# SparkFun_ProtoShield_Kit.net
KiCad netlist of a schematic drawn in EAGLE
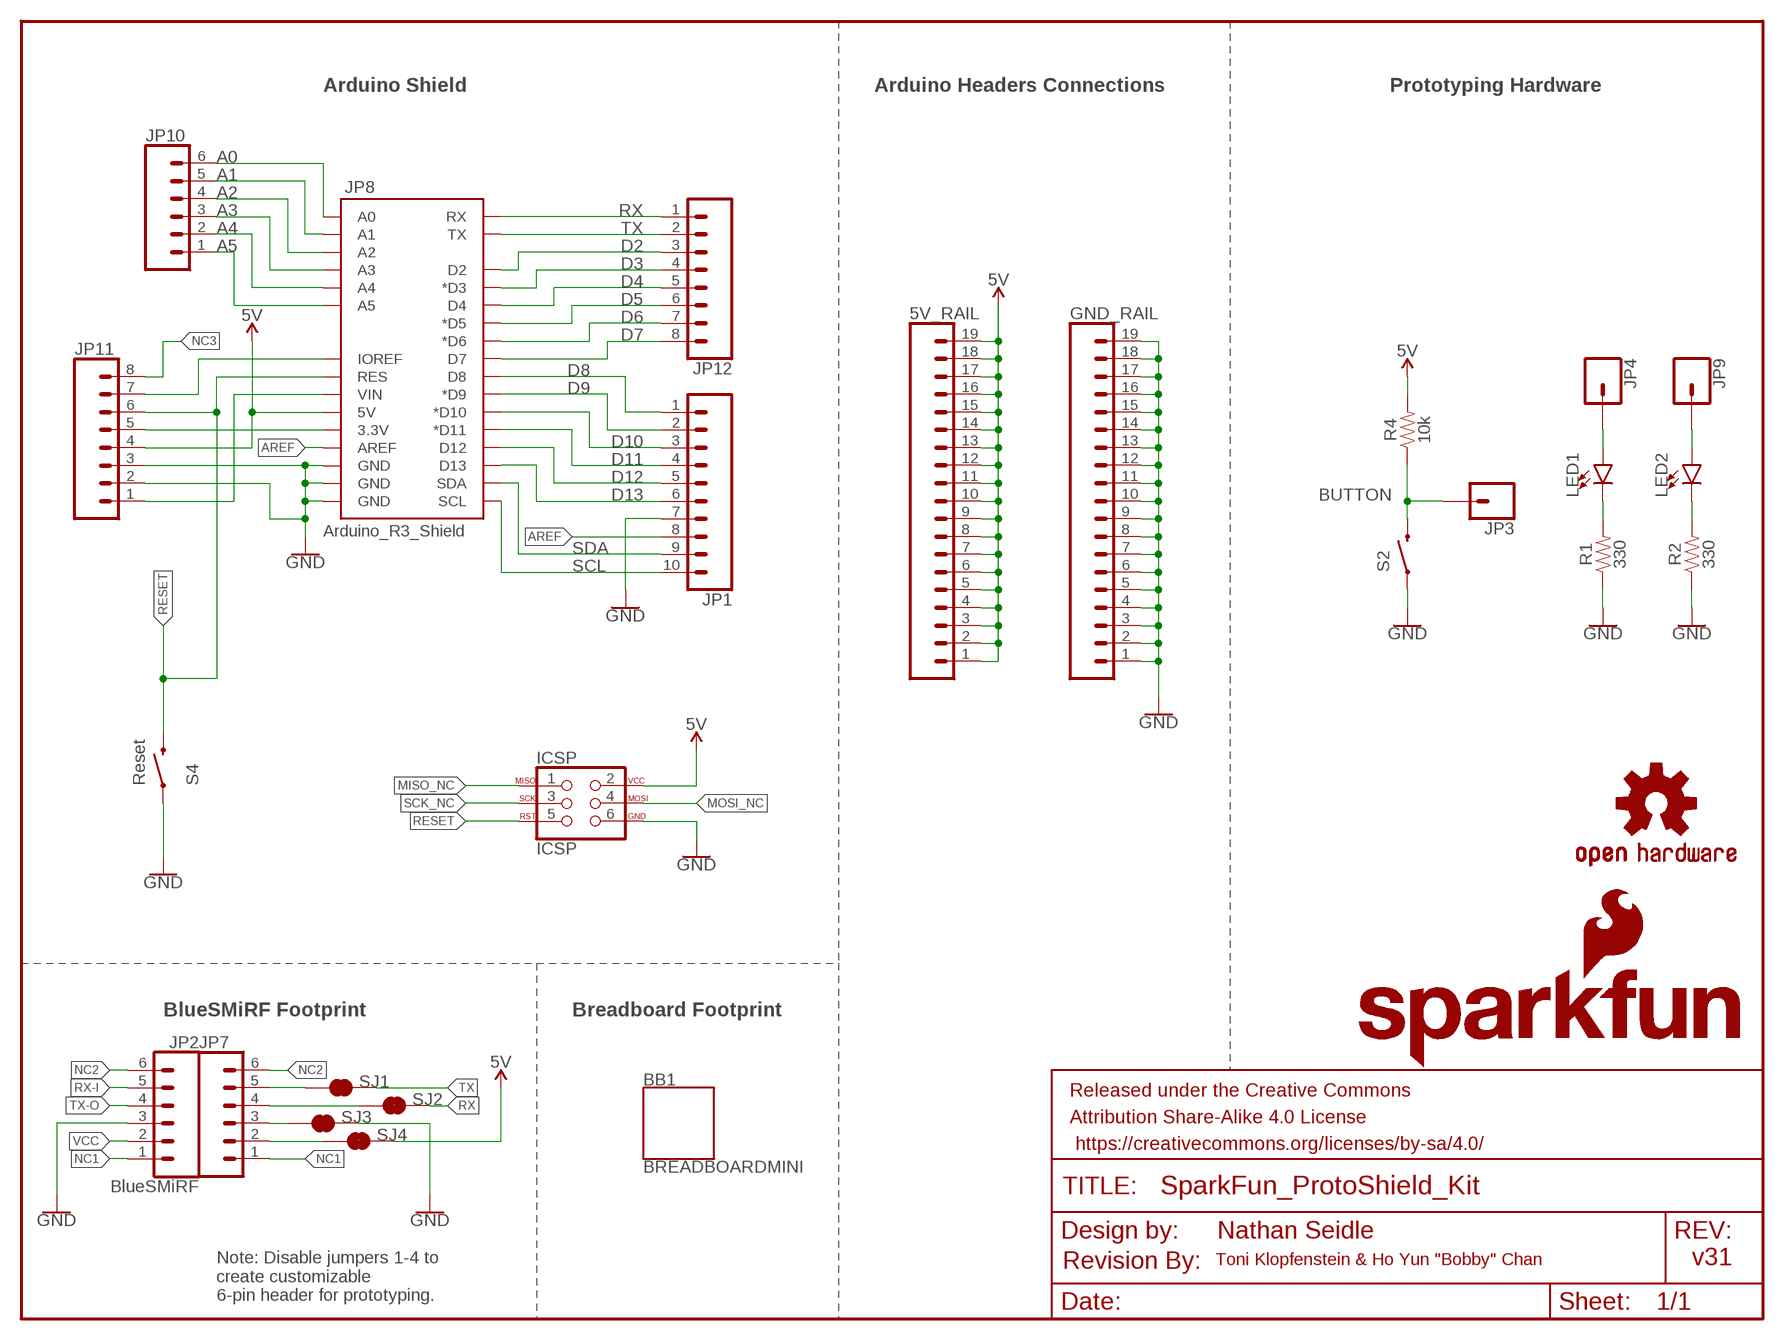
[diagram p0: schematic, sheet 1]

(export (version "E")
  (design (tool "Eeschema 10.0.6"))
  (components
    (comp (ref "5V_RAIL")
      (value "CONN_19")
      (footprint "eagle-import:1X19")
      (libsource (lib "eagle-import") (part "CONN_19"))
    )
    (comp (ref "BB1")
      (value "BREADBOARDMINI")
      (footprint "eagle-import:BREADBOARD-MINI")
      (libsource (lib "eagle-import") (part "BREADBOARDMINI"))
    )
    (comp (ref "FRAME1")
      (value "FRAME-LETTER")
      (footprint "eagle-import:CREATIVE_COMMONS")
      (libsource (lib "eagle-import") (part "FRAME-LETTER"))
    )
    (comp (ref "GND_RAIL")
      (value "CONN_19")
      (footprint "eagle-import:1X19")
      (libsource (lib "eagle-import") (part "CONN_19"))
    )
    (comp (ref "ICSP")
      (value "ICSP")
      (footprint "eagle-import:2X3")
      (libsource (lib "eagle-import") (part "AVR_SPI_PROG_3X2PTH"))
    )
    (comp (ref "JP1")
      (value "CONN_10\"")
      (footprint "eagle-import:1X10")
      (libsource (lib "eagle-import") (part "CONN_10{dblquote}"))
    )
    (comp (ref "JP2")
      (value "BlueSMiRF")
      (footprint "eagle-import:1X06")
      (libsource (lib "eagle-import") (part "CONN_06SILK_FEMALE_PTH"))
    )
    (comp (ref "JP3")
      (value "CONN_01")
      (footprint "eagle-import:1X01")
      (libsource (lib "eagle-import") (part "CONN_01"))
    )
    (comp (ref "JP4")
      (value "CONN_01")
      (footprint "eagle-import:1X01")
      (libsource (lib "eagle-import") (part "CONN_01"))
    )
    (comp (ref "JP7")
      (value "CONN_06SILK_FEMALE_PTH")
      (footprint "eagle-import:1X06")
      (libsource (lib "eagle-import") (part "CONN_06SILK_FEMALE_PTH"))
    )
    (comp (ref "JP8")
      (value "ARDUINO_R3_SHIELDR3_PROTO_SHIELD")
      (footprint "eagle-import:UNO_R3_PROTO_SHIELD")
      (libsource (lib "eagle-import") (part "ARDUINO_R3_SHIELDR3_PROTO_SHIELD"))
    )
    (comp (ref "JP9")
      (value "CONN_01")
      (footprint "eagle-import:1X01")
      (libsource (lib "eagle-import") (part "CONN_01"))
    )
    (comp (ref "JP10")
      (value "CONN_06SILK_FEMALE_PTH")
      (footprint "eagle-import:1X06")
      (libsource (lib "eagle-import") (part "CONN_06SILK_FEMALE_PTH"))
    )
    (comp (ref "JP11")
      (value "CONN_08\"")
      (footprint "eagle-import:1X08")
      (libsource (lib "eagle-import") (part "CONN_08{dblquote}"))
    )
    (comp (ref "JP12")
      (value "CONN_08\"")
      (footprint "eagle-import:1X08")
      (libsource (lib "eagle-import") (part "CONN_08{dblquote}"))
    )
    (comp (ref "LED1")
      (value "LED3MM")
      (footprint "eagle-import:LED_3MM")
      (libsource (lib "eagle-import") (part "LED3MM"))
    )
    (comp (ref "LED2")
      (value "LED3MM")
      (footprint "eagle-import:LED_3MM")
      (libsource (lib "eagle-import") (part "LED3MM"))
    )
    (comp (ref "LOGO1")
      (value "OSHW-LOGOS")
      (footprint "eagle-import:OSHW-LOGO-S")
      (libsource (lib "eagle-import") (part "OSHW-LOGOS"))
    )
    (comp (ref "R1")
      (value "330")
      (footprint "eagle-import:AXIAL-0.3")
      (libsource (lib "eagle-import") (part "330OHM-HORIZ-1/10W-5%"))
    )
    (comp (ref "R2")
      (value "330")
      (footprint "eagle-import:AXIAL-0.3")
      (libsource (lib "eagle-import") (part "330OHM-HORIZ-1/10W-5%"))
    )
    (comp (ref "R4")
      (value "10k")
      (footprint "eagle-import:AXIAL-0.3")
      (libsource (lib "eagle-import") (part "10KOHM-HORIZ-1/4W-5%"))
    )
    (comp (ref "S2")
      (value "MOMENTARY-SWITCH-SPST-PTH-6.0MM-KIT")
      (footprint "eagle-import:TACTILE_SWITCH_PTH_6.0MM_KIT")
      (libsource (lib "eagle-import") (part "MOMENTARY-SWITCH-SPST-PTH-6.0MM-KIT"))
    )
    (comp (ref "S4")
      (value "MOMENTARY-SWITCH-SPST-PTH-6.0MM-KIT")
      (footprint "eagle-import:TACTILE_SWITCH_PTH_6.0MM_KIT")
      (libsource (lib "eagle-import") (part "MOMENTARY-SWITCH-SPST-PTH-6.0MM-KIT"))
    )
    (comp (ref "SJ1")
      (value "JUMPER-SMT_2_NC_TRACE_SILK")
      (footprint "eagle-import:SMT-JUMPER_2_NC_TRACE_SILK")
      (libsource (lib "eagle-import") (part "JUMPER-SMT_2_NC_TRACE_SILK"))
    )
    (comp (ref "SJ2")
      (value "JUMPER-SMT_2_NC_TRACE_SILK")
      (footprint "eagle-import:SMT-JUMPER_2_NC_TRACE_SILK")
      (libsource (lib "eagle-import") (part "JUMPER-SMT_2_NC_TRACE_SILK"))
    )
    (comp (ref "SJ3")
      (value "JUMPER-SMT_2_NC_TRACE_SILK")
      (footprint "eagle-import:SMT-JUMPER_2_NC_TRACE_SILK")
      (libsource (lib "eagle-import") (part "JUMPER-SMT_2_NC_TRACE_SILK"))
    )
    (comp (ref "SJ4")
      (value "JUMPER-SMT_2_NC_TRACE_SILK")
      (footprint "eagle-import:SMT-JUMPER_2_NC_TRACE_SILK")
      (libsource (lib "eagle-import") (part "JUMPER-SMT_2_NC_TRACE_SILK"))
    )
    (comp (ref "U$1")
      (value "SFE_LOGO_NAME_FLAME.1_INCH")
      (footprint "eagle-import:SFE_LOGO_NAME_FLAME_.1")
      (libsource (lib "eagle-import") (part "SFE_LOGO_NAME_FLAME.1_INCH"))
    )
    (comp (ref "U$2")
      (value "REVISION")
      (footprint "eagle-import:REVISION")
      (libsource (lib "eagle-import") (part "REVISION"))
    )
  )
  (nets
    (net (code "1") (name "/BUTTON") (class "Default")
      (node (ref "JP3") (pin "1") (pinfunction "1_1") (pintype "passive"))
      (node (ref "R4") (pin "P$1") (pinfunction "1_P$1") (pintype "passive"))
      (node (ref "S2") (pin "3") (pinfunction "2_3") (pintype "passive"))
    )
    (net (code "2") (name "/D2") (class "Default")
      (node (ref "JP12") (pin "3") (pinfunction "3_3") (pintype "passive"))
      (node (ref "JP8") (pin "D2") (pinfunction "D2_D2") (pintype "bidirectional"))
    )
    (net (code "3") (name "/D3") (class "Default")
      (node (ref "JP12") (pin "4") (pinfunction "4_4") (pintype "passive"))
      (node (ref "JP8") (pin "D3") (pinfunction "*D3_D3") (pintype "bidirectional"))
    )
    (net (code "4") (name "/D4") (class "Default")
      (node (ref "JP12") (pin "5") (pinfunction "5_5") (pintype "passive"))
      (node (ref "JP8") (pin "D4") (pinfunction "D4_D4") (pintype "bidirectional"))
    )
    (net (code "5") (name "/D5") (class "Default")
      (node (ref "JP12") (pin "6") (pinfunction "6_6") (pintype "passive"))
      (node (ref "JP8") (pin "D5") (pinfunction "*D5_D5") (pintype "bidirectional"))
    )
    (net (code "6") (name "/D6") (class "Default")
      (node (ref "JP12") (pin "7") (pinfunction "7_7") (pintype "passive"))
      (node (ref "JP8") (pin "D6") (pinfunction "*D6_D6") (pintype "bidirectional"))
    )
    (net (code "7") (name "/D7") (class "Default")
      (node (ref "JP12") (pin "8") (pinfunction "8_8") (pintype "passive"))
      (node (ref "JP8") (pin "D7") (pinfunction "D7_D7") (pintype "bidirectional"))
    )
    (net (code "8") (name "/D8") (class "Default")
      (node (ref "JP1") (pin "1") (pinfunction "1_1") (pintype "passive"))
      (node (ref "JP8") (pin "D8") (pinfunction "D8_D8") (pintype "bidirectional"))
    )
    (net (code "9") (name "/D9") (class "Default")
      (node (ref "JP1") (pin "2") (pinfunction "2_2") (pintype "passive"))
      (node (ref "JP8") (pin "D9") (pinfunction "*D9_D9") (pintype "bidirectional"))
    )
    (net (code "10") (name "/D10") (class "Default")
      (node (ref "JP1") (pin "3") (pinfunction "3_3") (pintype "passive"))
      (node (ref "JP8") (pin "D10") (pinfunction "*D10_D10") (pintype "bidirectional"))
    )
    (net (code "11") (name "/D11") (class "Default")
      (node (ref "JP1") (pin "4") (pinfunction "4_4") (pintype "passive"))
      (node (ref "JP8") (pin "D11") (pinfunction "*D11_D11") (pintype "bidirectional"))
    )
    (net (code "12") (name "/D12") (class "Default")
      (node (ref "JP1") (pin "5") (pinfunction "5_5") (pintype "passive"))
      (node (ref "JP8") (pin "D12") (pinfunction "D12_D12") (pintype "bidirectional"))
    )
    (net (code "13") (name "/D13") (class "Default")
      (node (ref "JP1") (pin "6") (pinfunction "6_6") (pintype "passive"))
      (node (ref "JP8") (pin "D13") (pinfunction "D13_D13") (pintype "bidirectional"))
    )
    (net (code "14") (name "/SCL") (class "Default")
      (node (ref "JP1") (pin "10") (pinfunction "10_10") (pintype "passive"))
      (node (ref "JP8") (pin "SCL") (pinfunction "SCL_SCL") (pintype "bidirectional"))
    )
    (net (code "15") (name "/SDA") (class "Default")
      (node (ref "JP1") (pin "9") (pinfunction "9_9") (pintype "passive"))
      (node (ref "JP8") (pin "SDA") (pinfunction "SDA_SDA") (pintype "bidirectional"))
    )
    (net (code "16") (name "5V") (class "Default")
      (node (ref "5V_RAIL") (pin "1") (pinfunction "1_1") (pintype "passive"))
      (node (ref "5V_RAIL") (pin "10") (pinfunction "10_10") (pintype "passive"))
      (node (ref "5V_RAIL") (pin "11") (pinfunction "11_11") (pintype "passive"))
      (node (ref "5V_RAIL") (pin "12") (pinfunction "12_12") (pintype "passive"))
      (node (ref "5V_RAIL") (pin "13") (pinfunction "13_13") (pintype "passive"))
      (node (ref "5V_RAIL") (pin "14") (pinfunction "14_14") (pintype "passive"))
      (node (ref "5V_RAIL") (pin "15") (pinfunction "15_15") (pintype "passive"))
      (node (ref "5V_RAIL") (pin "16") (pinfunction "16_16") (pintype "passive"))
      (node (ref "5V_RAIL") (pin "17") (pinfunction "17_17") (pintype "passive"))
      (node (ref "5V_RAIL") (pin "18") (pinfunction "18_18") (pintype "passive"))
      (node (ref "5V_RAIL") (pin "19") (pinfunction "19_19") (pintype "passive"))
      (node (ref "5V_RAIL") (pin "2") (pinfunction "2_2") (pintype "passive"))
      (node (ref "5V_RAIL") (pin "3") (pinfunction "3_3") (pintype "passive"))
      (node (ref "5V_RAIL") (pin "4") (pinfunction "4_4") (pintype "passive"))
      (node (ref "5V_RAIL") (pin "5") (pinfunction "5_5") (pintype "passive"))
      (node (ref "5V_RAIL") (pin "6") (pinfunction "6_6") (pintype "passive"))
      (node (ref "5V_RAIL") (pin "7") (pinfunction "7_7") (pintype "passive"))
      (node (ref "5V_RAIL") (pin "8") (pinfunction "8_8") (pintype "passive"))
      (node (ref "5V_RAIL") (pin "9") (pinfunction "9_9") (pintype "passive"))
      (node (ref "ICSP") (pin "2") (pinfunction "2_2") (pintype "passive"))
      (node (ref "JP11") (pin "4") (pinfunction "4_4") (pintype "passive"))
      (node (ref "JP8") (pin "5V") (pinfunction "5V_5V") (pintype "bidirectional"))
      (node (ref "R4") (pin "P$2") (pinfunction "2_P$2") (pintype "passive"))
      (node (ref "SJ4") (pin "2") (pinfunction "2_2") (pintype "passive"))
    )
    (net (code "17") (name "AREF") (class "Default")
      (node (ref "JP1") (pin "8") (pinfunction "8_8") (pintype "passive"))
      (node (ref "JP8") (pin "AREF") (pinfunction "AREF_AREF") (pintype "bidirectional"))
    )
    (net (code "18") (name "GND") (class "Default")
      (node (ref "GND_RAIL") (pin "1") (pinfunction "1_1") (pintype "passive"))
      (node (ref "GND_RAIL") (pin "10") (pinfunction "10_10") (pintype "passive"))
      (node (ref "GND_RAIL") (pin "11") (pinfunction "11_11") (pintype "passive"))
      (node (ref "GND_RAIL") (pin "12") (pinfunction "12_12") (pintype "passive"))
      (node (ref "GND_RAIL") (pin "13") (pinfunction "13_13") (pintype "passive"))
      (node (ref "GND_RAIL") (pin "14") (pinfunction "14_14") (pintype "passive"))
      (node (ref "GND_RAIL") (pin "15") (pinfunction "15_15") (pintype "passive"))
      (node (ref "GND_RAIL") (pin "16") (pinfunction "16_16") (pintype "passive"))
      (node (ref "GND_RAIL") (pin "17") (pinfunction "17_17") (pintype "passive"))
      (node (ref "GND_RAIL") (pin "18") (pinfunction "18_18") (pintype "passive"))
      (node (ref "GND_RAIL") (pin "19") (pinfunction "19_19") (pintype "passive"))
      (node (ref "GND_RAIL") (pin "2") (pinfunction "2_2") (pintype "passive"))
      (node (ref "GND_RAIL") (pin "3") (pinfunction "3_3") (pintype "passive"))
      (node (ref "GND_RAIL") (pin "4") (pinfunction "4_4") (pintype "passive"))
      (node (ref "GND_RAIL") (pin "5") (pinfunction "5_5") (pintype "passive"))
      (node (ref "GND_RAIL") (pin "6") (pinfunction "6_6") (pintype "passive"))
      (node (ref "GND_RAIL") (pin "7") (pinfunction "7_7") (pintype "passive"))
      (node (ref "GND_RAIL") (pin "8") (pinfunction "8_8") (pintype "passive"))
      (node (ref "GND_RAIL") (pin "9") (pinfunction "9_9") (pintype "passive"))
      (node (ref "ICSP") (pin "6") (pinfunction "6_6") (pintype "passive"))
      (node (ref "JP1") (pin "7") (pinfunction "7_7") (pintype "passive"))
      (node (ref "JP11") (pin "2") (pinfunction "2_2") (pintype "passive"))
      (node (ref "JP11") (pin "3") (pinfunction "3_3") (pintype "passive"))
      (node (ref "JP2") (pin "3") (pinfunction "3_3") (pintype "passive"))
      (node (ref "JP7") (pin "3") (pinfunction "3_3") (pintype "passive"))
      (node (ref "JP8") (pin "GND@0") (pinfunction "GND_GND@0") (pintype "bidirectional"))
      (node (ref "JP8") (pin "GND@1") (pinfunction "GND_GND@1") (pintype "bidirectional"))
      (node (ref "JP8") (pin "GND@2") (pinfunction "GND_GND@2") (pintype "bidirectional"))
      (node (ref "R1") (pin "P$1") (pinfunction "1_P$1") (pintype "passive"))
      (node (ref "R2") (pin "P$1") (pinfunction "1_P$1") (pintype "passive"))
      (node (ref "S2") (pin "1") (pinfunction "1_1") (pintype "passive"))
      (node (ref "S4") (pin "1") (pinfunction "1_1") (pintype "passive"))
      (node (ref "SJ3") (pin "1") (pinfunction "1_1") (pintype "passive"))
      (node (ref "SJ3") (pin "2") (pinfunction "2_2") (pintype "passive"))
    )
    (net (code "19") (name "MISO_NC") (class "Default")
      (node (ref "ICSP") (pin "1") (pinfunction "1_1") (pintype "passive"))
    )
    (net (code "20") (name "MOSI_NC") (class "Default")
      (node (ref "ICSP") (pin "4") (pinfunction "4_4") (pintype "passive"))
    )
    (net (code "21") (name "NC1") (class "Default")
      (node (ref "JP2") (pin "1") (pinfunction "1_1") (pintype "passive"))
      (node (ref "JP7") (pin "1") (pinfunction "1_1") (pintype "passive"))
    )
    (net (code "22") (name "NC2") (class "Default")
      (node (ref "JP2") (pin "6") (pinfunction "6_6") (pintype "passive"))
      (node (ref "JP7") (pin "6") (pinfunction "6_6") (pintype "passive"))
    )
    (net (code "23") (name "NC3") (class "Default")
      (node (ref "JP11") (pin "8") (pinfunction "8_8") (pintype "passive"))
    )
    (net (code "24") (name "Net-(JP4-Pad1)") (class "Default")
      (node (ref "JP4") (pin "1") (pinfunction "1_1") (pintype "passive"))
      (node (ref "LED1") (pin "A") (pinfunction "A_A") (pintype "passive"))
    )
    (net (code "25") (name "Net-(JP9-Pad1)") (class "Default")
      (node (ref "JP9") (pin "1") (pinfunction "1_1") (pintype "passive"))
      (node (ref "LED2") (pin "A") (pinfunction "A_A") (pintype "passive"))
    )
    (net (code "26") (name "Net-(JP10-Pad1)") (class "Default")
      (node (ref "JP10") (pin "1") (pinfunction "1_1") (pintype "passive"))
      (node (ref "JP8") (pin "A5") (pinfunction "A5_A5") (pintype "bidirectional"))
    )
    (net (code "27") (name "Net-(JP10-Pad2)") (class "Default")
      (node (ref "JP10") (pin "2") (pinfunction "2_2") (pintype "passive"))
      (node (ref "JP8") (pin "A4") (pinfunction "A4_A4") (pintype "bidirectional"))
    )
    (net (code "28") (name "Net-(JP10-Pad3)") (class "Default")
      (node (ref "JP10") (pin "3") (pinfunction "3_3") (pintype "passive"))
      (node (ref "JP8") (pin "A3") (pinfunction "A3_A3") (pintype "bidirectional"))
    )
    (net (code "29") (name "Net-(JP10-Pad4)") (class "Default")
      (node (ref "JP10") (pin "4") (pinfunction "4_4") (pintype "passive"))
      (node (ref "JP8") (pin "A2") (pinfunction "A2_A2") (pintype "bidirectional"))
    )
    (net (code "30") (name "Net-(JP10-Pad5)") (class "Default")
      (node (ref "JP10") (pin "5") (pinfunction "5_5") (pintype "passive"))
      (node (ref "JP8") (pin "A1") (pinfunction "A1_A1") (pintype "bidirectional"))
    )
    (net (code "31") (name "Net-(JP10-Pad6)") (class "Default")
      (node (ref "JP10") (pin "6") (pinfunction "6_6") (pintype "passive"))
      (node (ref "JP8") (pin "A0") (pinfunction "A0_A0") (pintype "bidirectional"))
    )
    (net (code "32") (name "Net-(JP11-Pad1)") (class "Default")
      (node (ref "JP11") (pin "1") (pinfunction "1_1") (pintype "passive"))
      (node (ref "JP8") (pin "VIN") (pinfunction "VIN_VIN") (pintype "bidirectional"))
    )
    (net (code "33") (name "Net-(JP11-Pad5)") (class "Default")
      (node (ref "JP11") (pin "5") (pinfunction "5_5") (pintype "passive"))
      (node (ref "JP8") (pin "3.3V") (pinfunction "3.3V_3.3V") (pintype "bidirectional"))
    )
    (net (code "34") (name "Net-(JP11-Pad7)") (class "Default")
      (node (ref "JP11") (pin "7") (pinfunction "7_7") (pintype "passive"))
      (node (ref "JP8") (pin "IOREF") (pinfunction "IOREF_IOREF") (pintype "bidirectional"))
    )
    (net (code "35") (name "Net-(LED1-C)") (class "Default")
      (node (ref "LED1") (pin "K") (pinfunction "C_K") (pintype "passive"))
      (node (ref "R1") (pin "P$2") (pinfunction "2_P$2") (pintype "passive"))
    )
    (net (code "36") (name "Net-(LED2-C)") (class "Default")
      (node (ref "LED2") (pin "K") (pinfunction "C_K") (pintype "passive"))
      (node (ref "R2") (pin "P$2") (pinfunction "2_P$2") (pintype "passive"))
    )
    (net (code "37") (name "RESET") (class "Default")
      (node (ref "ICSP") (pin "5") (pinfunction "5_5") (pintype "passive"))
      (node (ref "JP11") (pin "6") (pinfunction "6_6") (pintype "passive"))
      (node (ref "JP8") (pin "RES") (pinfunction "RES_RES") (pintype "bidirectional"))
      (node (ref "S4") (pin "3") (pinfunction "2_3") (pintype "passive"))
    )
    (net (code "38") (name "RX") (class "Default")
      (node (ref "JP12") (pin "1") (pinfunction "1_1") (pintype "passive"))
      (node (ref "JP8") (pin "RX") (pinfunction "RX_RX") (pintype "bidirectional"))
      (node (ref "SJ2") (pin "2") (pinfunction "2_2") (pintype "passive"))
    )
    (net (code "39") (name "RX-I") (class "Default")
      (node (ref "JP2") (pin "5") (pinfunction "5_5") (pintype "passive"))
      (node (ref "JP7") (pin "5") (pinfunction "5_5") (pintype "passive"))
      (node (ref "SJ1") (pin "1") (pinfunction "1_1") (pintype "passive"))
    )
    (net (code "40") (name "SCK_NC") (class "Default")
      (node (ref "ICSP") (pin "3") (pinfunction "3_3") (pintype "passive"))
    )
    (net (code "41") (name "TX") (class "Default")
      (node (ref "JP12") (pin "2") (pinfunction "2_2") (pintype "passive"))
      (node (ref "JP8") (pin "TX") (pinfunction "TX_TX") (pintype "bidirectional"))
      (node (ref "SJ1") (pin "2") (pinfunction "2_2") (pintype "passive"))
    )
    (net (code "42") (name "TX-O") (class "Default")
      (node (ref "JP2") (pin "4") (pinfunction "4_4") (pintype "passive"))
      (node (ref "JP7") (pin "4") (pinfunction "4_4") (pintype "passive"))
      (node (ref "SJ2") (pin "1") (pinfunction "1_1") (pintype "passive"))
    )
    (net (code "43") (name "VCC") (class "Default")
      (node (ref "JP2") (pin "2") (pinfunction "2_2") (pintype "passive"))
      (node (ref "JP7") (pin "2") (pinfunction "2_2") (pintype "passive"))
      (node (ref "SJ4") (pin "1") (pinfunction "1_1") (pintype "passive"))
    )
  )
)
